# current_sense.net
KiCad netlist of a schematic drawn in Altium Designer
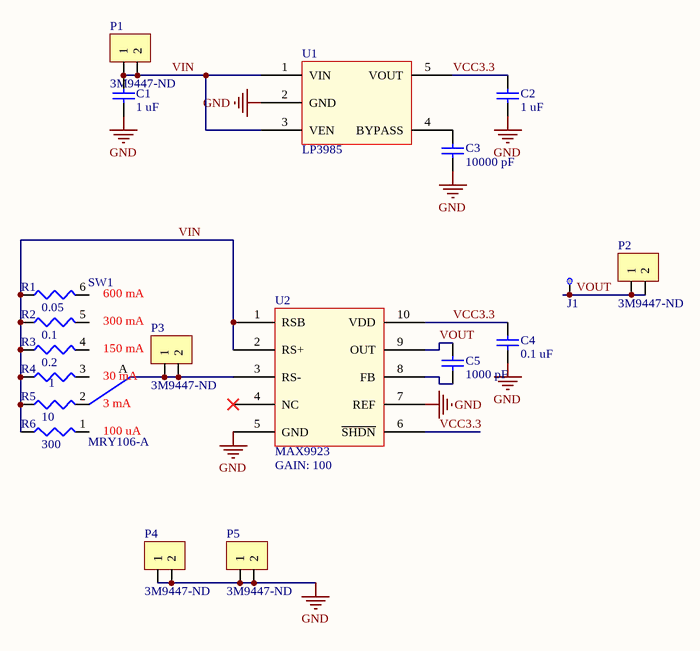
[diagram p0: current_sense.SchDoc]

(export (version "E")
  (design (tool "Eeschema 10.0.6"))
  (components
    (comp (ref "C1")
      (value "1 uF")
      (footprint "0603")
      (description "Ceramic capacitor, 1 uF, 0603 package")
      (fields (field (name "TOLERANCE") "10%") (field (name "Comment") "Ceramic capacitor"))
      (libsource (lib "rlc") (part "C_1u_0603_ceramic"))
    )
    (comp (ref "C2")
      (value "1 uF")
      (footprint "0603")
      (description "Ceramic capacitor, 1 uF, 0603 package")
      (fields (field (name "TOLERANCE") "10%") (field (name "Comment") "Ceramic capacitor"))
      (libsource (lib "rlc") (part "C_1u_0603_ceramic"))
    )
    (comp (ref "C3")
      (value "10000 pF")
      (footprint "0603")
      (description "Ceramic capacitor, 10000 pF, 0603 package")
      (fields (field (name "TOLERANCE") "10%") (field (name "Comment") "Ceramic capacitor"))
      (libsource (lib "rlc") (part "C_10000p_0603_ceramic"))
    )
    (comp (ref "C4")
      (value "0.1 uF")
      (footprint "0603")
      (description "Ceramic capacitor, 0.1 uF, 0603 package")
      (fields (field (name "TOLERANCE") "10%") (field (name "Comment") "Ceramic capacitor"))
      (libsource (lib "rlc") (part "C_0.1u_0603_ceramic"))
    )
    (comp (ref "C5")
      (value "1000 pF")
      (footprint "0603")
      (description "Ceramic capacitor, 1000 pF, 0603 package")
      (fields (field (name "TOLERANCE") "10%") (field (name "Comment") "Ceramic capacitor"))
      (libsource (lib "rlc") (part "C_1000p_0603_ceramic"))
    )
    (comp (ref "J1")
      (value "5004")
      (footprint "TestPoint")
      (description "TEST POINT PC MINI .040\"D YELLOW")
      (libsource (lib "current_sense") (part "TestPoint"))
    )
    (comp (ref "P1")
      (value "1 x 2 header")
      (footprint "1x2 header")
      (description "100 mils standard header")
      (fields (field (name "SUPPLIER PART NUMBER 1") "3M9447-ND"))
      (libsource (lib "current_sense") (part "1 x 2 header"))
    )
    (comp (ref "P2")
      (value "1 x 2 header")
      (footprint "1x2 header")
      (description "100 mils standard header")
      (fields (field (name "SUPPLIER PART NUMBER 1") "3M9447-ND"))
      (libsource (lib "current_sense") (part "1 x 2 header"))
    )
    (comp (ref "P3")
      (value "1 x 2 header")
      (footprint "1x2 header")
      (description "100 mils standard header")
      (fields (field (name "SUPPLIER PART NUMBER 1") "3M9447-ND"))
      (libsource (lib "current_sense") (part "1 x 2 header"))
    )
    (comp (ref "P4")
      (value "1 x 2 header")
      (footprint "1x2 header")
      (description "100 mils standard header")
      (fields (field (name "SUPPLIER PART NUMBER 1") "3M9447-ND"))
      (libsource (lib "current_sense") (part "1 x 2 header"))
    )
    (comp (ref "P5")
      (value "1 x 2 header")
      (footprint "1x2 header")
      (description "100 mils standard header")
      (fields (field (name "SUPPLIER PART NUMBER 1") "3M9447-ND"))
      (libsource (lib "current_sense") (part "1 x 2 header"))
    )
    (comp (ref "R1")
      (value "0.05")
      (footprint "C1206")
      (description "Resistor")
      (fields (field (name "Comment") "Res3") (field (name "PUBLISHER") "Altium Limited"))
      (libsource (lib "Miscellaneous Devices") (part "Res3"))
    )
    (comp (ref "R2")
      (value "0.1")
      (footprint "VCS1610")
      (description "Resistor")
      (fields (field (name "Comment") "Res3") (field (name "PUBLISHER") "Altium Limited"))
      (libsource (lib "Miscellaneous Devices") (part "Res3"))
    )
    (comp (ref "R3")
      (value "0.2")
      (footprint "CSM3637")
      (description "Resistor")
      (fields (field (name "Comment") "Res3") (field (name "PUBLISHER") "Altium Limited"))
      (libsource (lib "Miscellaneous Devices") (part "Res3"))
    )
    (comp (ref "R4")
      (value "1")
      (footprint "VCS1610")
      (description "Resistor")
      (fields (field (name "Comment") "Res3") (field (name "PUBLISHER") "Altium Limited"))
      (libsource (lib "Miscellaneous Devices") (part "Res3"))
    )
    (comp (ref "R5")
      (value "10")
      (footprint "6-0805_N")
      (description "Resistor")
      (fields (field (name "Comment") "Res3") (field (name "PUBLISHER") "Altium Limited"))
      (libsource (lib "Miscellaneous Devices") (part "Res3"))
    )
    (comp (ref "R6")
      (value "300")
      (footprint "6-0805_N")
      (description "Resistor")
      (fields (field (name "Comment") "Res3") (field (name "PUBLISHER") "Altium Limited"))
      (libsource (lib "Miscellaneous Devices") (part "Res3"))
    )
    (comp (ref "SW1")
      (value "MRY106-A")
      (footprint "MRY switch")
      (description "SW ROTARY SP BLK KNOB 125V")
      (libsource (lib "current_sense") (part "MRY106-A"))
    )
    (comp (ref "U1")
      (value "LP3985")
      (footprint "SOT23-5")
      (description "150mA Low-Noise Ultra Low-Dropout CMOS Voltage Regulator")
      (libsource (lib "current_sense") (part "LP3985"))
    )
    (comp (ref "U2")
      (value "MAX9923")
      (footprint "10umax")
      (description "ultra-precision, high-side current-sense amplifier")
      (fields (field (name "GAIN") "100"))
      (libsource (lib "current_sense") (part "MAX9923"))
    )
  )
  (nets
    (net (code "1") (name "/VCC3.3") (class "Default")
      (node (ref "C2") (pin "1") (pintype "passive"))
      (node (ref "C4") (pin "1") (pintype "passive"))
      (node (ref "U1") (pin "5") (pinfunction "VOUT_5") (pintype "passive"))
      (node (ref "U2") (pin "10") (pinfunction "VDD_10") (pintype "passive"))
      (node (ref "U2") (pin "6") (pinfunction "~{SHDN}_6") (pintype "passive"))
    )
    (net (code "2") (name "/VIN") (class "Default")
      (node (ref "C1") (pin "1") (pintype "passive"))
      (node (ref "P1") (pin "1") (pinfunction "1_1") (pintype "passive"))
      (node (ref "P1") (pin "2") (pinfunction "2_2") (pintype "passive"))
      (node (ref "R1") (pin "1") (pinfunction "1_1") (pintype "passive"))
      (node (ref "R2") (pin "1") (pinfunction "1_1") (pintype "passive"))
      (node (ref "R3") (pin "1") (pinfunction "1_1") (pintype "passive"))
      (node (ref "R4") (pin "1") (pinfunction "1_1") (pintype "passive"))
      (node (ref "R5") (pin "1") (pinfunction "1_1") (pintype "passive"))
      (node (ref "R6") (pin "1") (pinfunction "1_1") (pintype "passive"))
      (node (ref "U1") (pin "1") (pinfunction "VIN_1") (pintype "passive"))
      (node (ref "U1") (pin "3") (pinfunction "VEN_3") (pintype "passive"))
      (node (ref "U2") (pin "1") (pinfunction "RSB_1") (pintype "passive"))
      (node (ref "U2") (pin "2") (pinfunction "RS+_2") (pintype "passive"))
    )
    (net (code "3") (name "/VOUT") (class "Default")
      (node (ref "C5") (pin "1") (pintype "passive"))
      (node (ref "J1") (pin "1") (pinfunction "TB_1") (pintype "passive"))
      (node (ref "P2") (pin "1") (pinfunction "1_1") (pintype "passive"))
      (node (ref "P2") (pin "2") (pinfunction "2_2") (pintype "passive"))
      (node (ref "U2") (pin "9") (pinfunction "OUT_9") (pintype "passive"))
    )
    (net (code "4") (name "GND") (class "Default")
      (node (ref "C1") (pin "2") (pintype "passive"))
      (node (ref "C2") (pin "2") (pintype "passive"))
      (node (ref "C3") (pin "2") (pintype "passive"))
      (node (ref "C4") (pin "2") (pintype "passive"))
      (node (ref "P4") (pin "1") (pinfunction "1_1") (pintype "passive"))
      (node (ref "P4") (pin "2") (pinfunction "2_2") (pintype "passive"))
      (node (ref "P5") (pin "1") (pinfunction "1_1") (pintype "passive"))
      (node (ref "P5") (pin "2") (pinfunction "2_2") (pintype "passive"))
      (node (ref "U1") (pin "2") (pinfunction "GND_2") (pintype "passive"))
      (node (ref "U2") (pin "5") (pinfunction "GND_5") (pintype "passive"))
      (node (ref "U2") (pin "7") (pinfunction "REF_7") (pintype "passive"))
    )
    (net (code "5") (name "Net-(R1-Pad2)") (class "Default")
      (node (ref "R1") (pin "2") (pinfunction "2_2") (pintype "passive"))
      (node (ref "SW1") (pin "6") (pinfunction "6_6") (pintype "passive"))
    )
    (net (code "6") (name "Net-(R2-Pad2)") (class "Default")
      (node (ref "R2") (pin "2") (pinfunction "2_2") (pintype "passive"))
      (node (ref "SW1") (pin "5") (pinfunction "5_5") (pintype "passive"))
    )
    (net (code "7") (name "Net-(R3-Pad2)") (class "Default")
      (node (ref "R3") (pin "2") (pinfunction "2_2") (pintype "passive"))
      (node (ref "SW1") (pin "4") (pinfunction "4_4") (pintype "passive"))
    )
    (net (code "8") (name "Net-(R4-Pad2)") (class "Default")
      (node (ref "R4") (pin "2") (pinfunction "2_2") (pintype "passive"))
      (node (ref "SW1") (pin "3") (pinfunction "3_3") (pintype "passive"))
    )
    (net (code "9") (name "Net-(R5-Pad2)") (class "Default")
      (node (ref "R5") (pin "2") (pinfunction "2_2") (pintype "passive"))
      (node (ref "SW1") (pin "2") (pinfunction "2_2") (pintype "passive"))
    )
    (net (code "10") (name "Net-(R6-Pad2)") (class "Default")
      (node (ref "R6") (pin "2") (pinfunction "2_2") (pintype "passive"))
      (node (ref "SW1") (pin "1") (pinfunction "1_1") (pintype "passive"))
    )
    (net (code "11") (name "Net-(U1-BYPASS)") (class "Default")
      (node (ref "C3") (pin "1") (pintype "passive"))
      (node (ref "U1") (pin "4") (pinfunction "BYPASS_4") (pintype "passive"))
    )
    (net (code "12") (name "Net-(U2-FB)") (class "Default")
      (node (ref "C5") (pin "2") (pintype "passive"))
      (node (ref "U2") (pin "8") (pinfunction "FB_8") (pintype "passive"))
    )
    (net (code "13") (name "Net-(U2-RS-)") (class "Default")
      (node (ref "P3") (pin "1") (pinfunction "1_1") (pintype "passive"))
      (node (ref "P3") (pin "2") (pinfunction "2_2") (pintype "passive"))
      (node (ref "SW1") (pin "A") (pinfunction "A_A") (pintype "passive"))
      (node (ref "U2") (pin "3") (pinfunction "RS-_3") (pintype "passive"))
    )
    (net (code "14") (name "unconnected-(U2-NC-Pad4)") (class "Default")
      (node (ref "U2") (pin "4") (pinfunction "NC_4") (pintype "passive+no_connect"))
    )
  )
)
